# ClosedLoop_Drive_MC_Sensors.net
KiCad netlist of a schematic drawn in Altium Designer
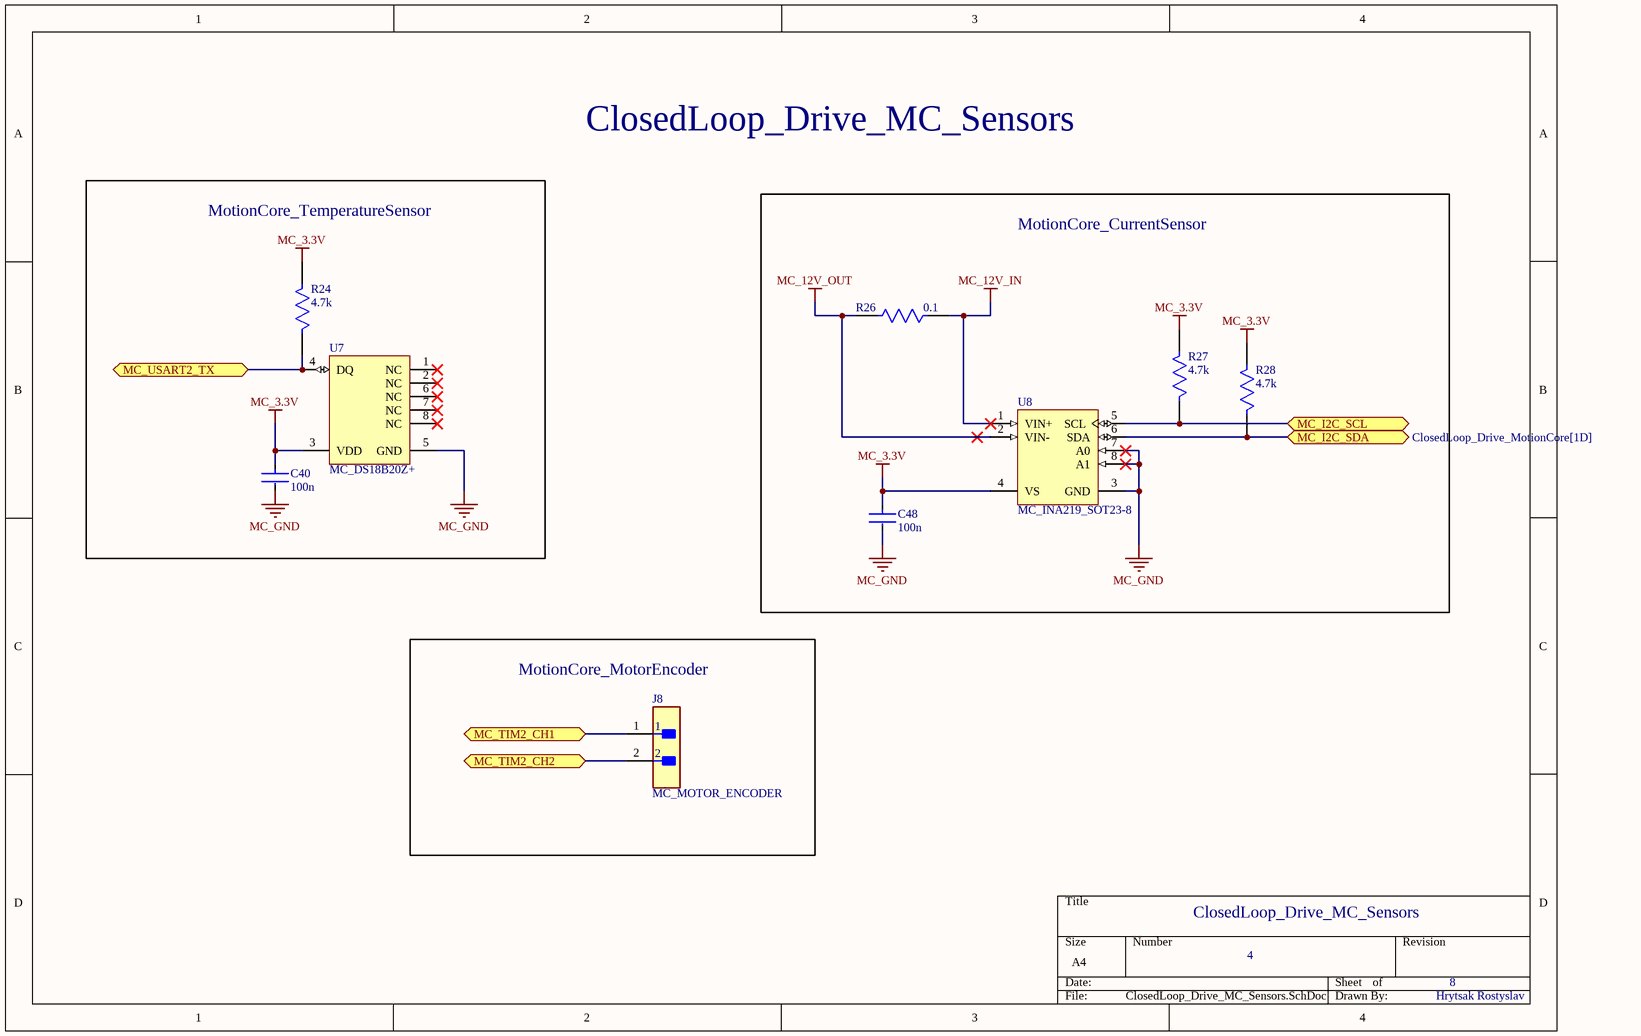
[diagram p0: ClosedLoop_Drive_MC_Sensors.SchDoc]

(export (version "E")
  (design (tool "Eeschema 10.0.6"))
  (components
    (comp (ref "C40")
      (value "100n")
      (footprint "FP-0805-L_2_01_0_2-W_1_25-MFG")
      (description "0805")
      (fields (field (name "TOLERANCE") "10%"))
      (libsource (lib "Altium Content Vault") (part "b4654b650e69147ec39a6b967a45e02"))
    )
    (comp (ref "C48")
      (value "100n")
      (footprint "FP-0805-L_2_01_0_2-W_1_25-MFG")
      (description "0805")
      (fields (field (name "TOLERANCE") "10%"))
      (libsource (lib "Altium Content Vault") (part "b4654b650e69147ec39a6b967a45e02"))
    )
    (comp (ref "J8")
      (value "MC_MOTOR_ENCODER")
      (footprint "FP-TSW-102-07-F-S-MFG")
      (description "CONN HEADER VERT 2POS 2.54MM")
      (libsource (lib "Altium Content Vault") (part "3bc925449376181038e59eaffc5286c"))
    )
    (comp (ref "R24")
      (value "4.7k")
      (footprint "FP-MCU0805-IPC_A")
      (description "0805")
      (fields (field (name "TOLERANCE") "0.5%"))
      (libsource (lib "Altium Content Vault") (part "1029c3af85768c4190bb7ad29bc67b5"))
    )
    (comp (ref "R26")
      (value "0.1")
      (footprint "FP-CRA2512-IPC_C")
      (description "RES 0.1 OHM 1% 3W 2512")
      (libsource (lib "Altium Content Vault") (part "1029c3af85768c4190bb7ad29bc67b5"))
    )
    (comp (ref "R27")
      (value "4.7k")
      (footprint "FP-MCU0805-IPC_A")
      (description "0805")
      (fields (field (name "TOLERANCE") "0.5%"))
      (libsource (lib "Altium Content Vault") (part "1029c3af85768c4190bb7ad29bc67b5"))
    )
    (comp (ref "R28")
      (value "4.7k")
      (footprint "FP-MCU0805-IPC_A")
      (description "0805")
      (fields (field (name "TOLERANCE") "0.5%"))
      (libsource (lib "Altium Content Vault") (part "1029c3af85768c4190bb7ad29bc67b5"))
    )
    (comp (ref "U7")
      (value "MC_DS18B20Z+")
      (footprint "MAXM-S8+2_L")
      (description "High-Precision 1-Wire Digital Thermometer, -55 to 125 degC, 8-Pin SOIC (S8+2), Pb-Free")
      (fields (field (name "PARTNUMBER") "DS18B20Z+") (field (name "GENERIC PART NUMBER") "DS18B20"))
      (libsource (lib "Altium Content Vault") (part "DS18B20-S8+2"))
    )
    (comp (ref "U8")
      (value "MC_INA219_SOT23-8")
      (footprint "DCN0008A_L")
      (fields (field (name "MANUFACTURER") "Texas Instruments") (field (name "PARTNUMBER") "INA219AIDCNT"))
      (libsource (lib "Altium Content Vault") (part "TI-INA219DCN8"))
    )
  )
  (nets
    (net (code "1") (name "/MC_I2C_SCL") (class "Default")
      (node (ref "R27") (pin "1") (pinfunction "1_1") (pintype "passive"))
      (node (ref "U8") (pin "5") (pinfunction "SCL_5") (pintype "bidirectional"))
    )
    (net (code "2") (name "/MC_I2C_SDA") (class "Default")
      (node (ref "R28") (pin "1") (pinfunction "1_1") (pintype "passive"))
      (node (ref "U8") (pin "6") (pinfunction "SDA_6") (pintype "bidirectional"))
    )
    (net (code "3") (name "/MC_TIM2_CH1") (class "Default")
      (node (ref "J8") (pin "1") (pinfunction "1_1") (pintype "passive"))
    )
    (net (code "4") (name "/MC_TIM2_CH2") (class "Default")
      (node (ref "J8") (pin "2") (pinfunction "2_2") (pintype "passive"))
    )
    (net (code "5") (name "/MC_USART2_TX") (class "Default")
      (node (ref "R24") (pin "1") (pinfunction "1_1") (pintype "passive"))
      (node (ref "U7") (pin "4") (pinfunction "DQ_4") (pintype "bidirectional"))
    )
    (net (code "6") (name "MC_3.3V") (class "Default")
      (node (ref "C40") (pin "1") (pinfunction "1_1") (pintype "passive"))
      (node (ref "C48") (pin "1") (pinfunction "1_1") (pintype "passive"))
      (node (ref "R24") (pin "2") (pinfunction "2_2") (pintype "passive"))
      (node (ref "R27") (pin "2") (pinfunction "2_2") (pintype "passive"))
      (node (ref "R28") (pin "2") (pinfunction "2_2") (pintype "passive"))
      (node (ref "U7") (pin "3") (pinfunction "VDD_3") (pintype "power_in"))
      (node (ref "U8") (pin "4") (pinfunction "VS_4") (pintype "power_in"))
    )
    (net (code "7") (name "MC_12V_IN") (class "Default")
      (node (ref "R26") (pin "1") (pinfunction "1_1") (pintype "passive"))
      (node (ref "U8") (pin "1") (pinfunction "VIN+_1") (pintype "input"))
    )
    (net (code "8") (name "MC_12V_OUT") (class "Default")
      (node (ref "R26") (pin "2") (pinfunction "2_2") (pintype "passive"))
      (node (ref "U8") (pin "2") (pinfunction "VIN-_2") (pintype "input"))
    )
    (net (code "9") (name "MC_GND") (class "Default")
      (node (ref "C40") (pin "2") (pinfunction "2_2") (pintype "passive"))
      (node (ref "C48") (pin "2") (pinfunction "2_2") (pintype "passive"))
      (node (ref "U7") (pin "5") (pinfunction "GND_5") (pintype "power_in"))
      (node (ref "U8") (pin "3") (pinfunction "GND_3") (pintype "power_in"))
      (node (ref "U8") (pin "7") (pinfunction "A0_7") (pintype "input"))
      (node (ref "U8") (pin "8") (pinfunction "A1_8") (pintype "input"))
    )
    (net (code "10") (name "unconnected-(U7-NC-Pad1)") (class "Default")
      (node (ref "U7") (pin "1") (pinfunction "NC_1") (pintype "passive+no_connect"))
    )
    (net (code "11") (name "unconnected-(U7-NC-Pad2)") (class "Default")
      (node (ref "U7") (pin "2") (pinfunction "NC_2") (pintype "passive+no_connect"))
    )
    (net (code "12") (name "unconnected-(U7-NC-Pad6)") (class "Default")
      (node (ref "U7") (pin "6") (pinfunction "NC_6") (pintype "passive+no_connect"))
    )
    (net (code "13") (name "unconnected-(U7-NC-Pad7)") (class "Default")
      (node (ref "U7") (pin "7") (pinfunction "NC_7") (pintype "passive+no_connect"))
    )
    (net (code "14") (name "unconnected-(U7-NC-Pad8)") (class "Default")
      (node (ref "U7") (pin "8") (pinfunction "NC_8") (pintype "passive+no_connect"))
    )
  )
)
